# POWER.net
KiCad netlist of a schematic drawn in Altium Designer
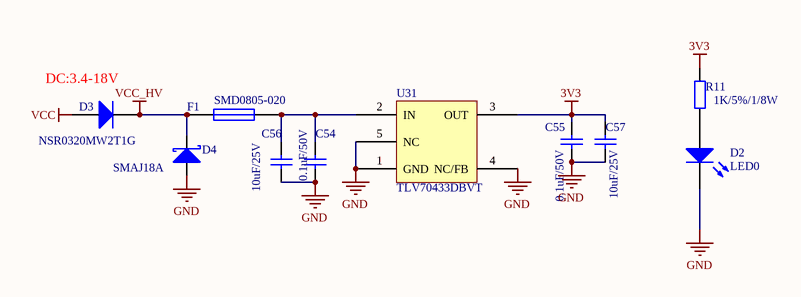
[diagram p0: POWER.SchDoc]

(export (version "E")
  (design (tool "Eeschema 10.0.6"))
  (components
    (comp (ref "C54")
      (value "0.1uF/50V")
      (footprint "0402C")
      (description "Capacitor")
      (fields (field (name "PUBLISHER") "Altium Limited"))
      (libsource (lib "Miscellaneous Devices") (part "Cap"))
    )
    (comp (ref "C55")
      (value "0.1uF/50V")
      (footprint "0402C")
      (description "Capacitor")
      (fields (field (name "PUBLISHER") "Altium Limited"))
      (libsource (lib "Miscellaneous Devices") (part "Cap"))
    )
    (comp (ref "C56")
      (value "10uF/25V")
      (footprint "0402C")
      (description "Capacitor")
      (fields (field (name "PUBLISHER") "Altium Limited"))
      (libsource (lib "Miscellaneous Devices") (part "Cap"))
    )
    (comp (ref "C57")
      (value "10uF/25V")
      (footprint "0402C")
      (description "Capacitor")
      (fields (field (name "PUBLISHER") "Altium Limited"))
      (libsource (lib "Miscellaneous Devices") (part "Cap"))
    )
    (comp (ref "D2")
      (value "LED0")
      (footprint "0603LED")
      (description "Typical INFRARED GaAs LED")
      (fields (field (name "PUBLISHER") "Altium Limited"))
      (libsource (lib "Miscellaneous Devices") (part "LED0"))
    )
    (comp (ref "D3")
      (value "NSR0320MW2T1G")
      (footprint "sod323")
      (description "Default Diode")
      (fields (field (name "PUBLISHER") "Altium Limited"))
      (libsource (lib "Miscellaneous Devices") (part "Diode"))
    )
    (comp (ref "D4")
      (value "SMAJ18A")
      (footprint "SMa")
      (description "Schottky Diode")
      (libsource (lib "*") (part "DIODE S"))
    )
    (comp (ref "F1")
      (value "SMD0805-020")
      (footprint "0805R")
      (description "Fuse")
      (fields (field (name "PUBLISHER") "Altium Limited"))
      (libsource (lib "Miscellaneous Devices") (part "Fuse 1"))
    )
    (comp (ref "R11")
      (value "1K/5%/1/8W")
      (footprint "0402R")
      (description "Resistor")
      (fields (field (name "PUBLISHER") "Altium Limited"))
      (libsource (lib "Miscellaneous Devices") (part "Res2"))
    )
    (comp (ref "U31")
      (value "TLV70433DBVT")
      (footprint "SOT23-5(DBV)")
      (libsource (lib "JRJ") (part "TPS76318"))
    )
  )
  (nets
    (net (code "1") (name "3V3") (class "Default")
      (node (ref "C55") (pin "1") (pinfunction "1_1") (pintype "passive"))
      (node (ref "C57") (pin "2") (pinfunction "2_2") (pintype "passive"))
      (node (ref "R11") (pin "1") (pinfunction "1_1") (pintype "passive"))
      (node (ref "U31") (pin "3") (pinfunction "OUT_3") (pintype "passive"))
    )
    (net (code "2") (name "GND") (class "Default")
      (node (ref "C54") (pin "2") (pinfunction "2_2") (pintype "passive"))
      (node (ref "C55") (pin "2") (pinfunction "2_2") (pintype "passive"))
      (node (ref "C56") (pin "1") (pinfunction "1_1") (pintype "passive"))
      (node (ref "C57") (pin "1") (pinfunction "1_1") (pintype "passive"))
      (node (ref "D2") (pin "2") (pinfunction "K_2") (pintype "passive"))
      (node (ref "D4") (pin "1") (pinfunction "A_1") (pintype "passive"))
      (node (ref "U31") (pin "1") (pinfunction "GND_1") (pintype "passive"))
      (node (ref "U31") (pin "4") (pinfunction "NC/FB_4") (pintype "passive"))
      (node (ref "U31") (pin "5") (pinfunction "NC_5") (pintype "passive"))
    )
    (net (code "3") (name "Net-(D2-A)") (class "Default")
      (node (ref "D2") (pin "1") (pinfunction "A_1") (pintype "passive"))
      (node (ref "R11") (pin "2") (pinfunction "2_2") (pintype "passive"))
    )
    (net (code "4") (name "Net-(U31-IN)") (class "Default")
      (node (ref "C54") (pin "1") (pinfunction "1_1") (pintype "passive"))
      (node (ref "C56") (pin "2") (pinfunction "2_2") (pintype "passive"))
      (node (ref "F1") (pin "2") (pinfunction "2_2") (pintype "passive"))
      (node (ref "U31") (pin "2") (pinfunction "IN_2") (pintype "passive"))
    )
    (net (code "5") (name "VCC") (class "Default")
      (node (ref "D3") (pin "A") (pinfunction "A_A") (pintype "passive"))
    )
    (net (code "6") (name "VCC_HV") (class "Default")
      (node (ref "D3") (pin "K") (pinfunction "K_K") (pintype "passive"))
      (node (ref "D4") (pin "2") (pinfunction "K_2") (pintype "passive"))
      (node (ref "F1") (pin "1") (pinfunction "1_1") (pintype "passive"))
    )
  )
)
